# SCFschem.net
KiCad netlist of a schematic drawn in EAGLE
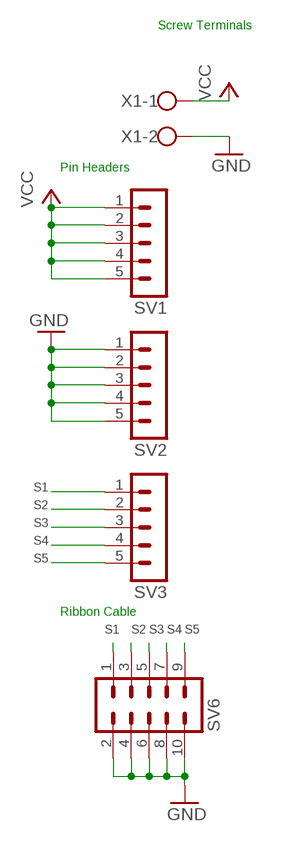
[diagram p0: schematic, sheet 1]

(export (version "E")
  (design (tool "Eeschema 10.0.6"))
  (components
    (comp (ref "SV1")
      (value "MA05-1")
      (footprint "eagle-import:MA05-1")
      (libsource (lib "eagle-import") (part "MA05-1"))
    )
    (comp (ref "SV2")
      (value "MA05-1")
      (footprint "eagle-import:MA05-1")
      (libsource (lib "eagle-import") (part "MA05-1"))
    )
    (comp (ref "SV3")
      (value "MA05-1")
      (footprint "eagle-import:MA05-1")
      (libsource (lib "eagle-import") (part "MA05-1"))
    )
    (comp (ref "SV6")
      (value "MA05-2")
      (footprint "eagle-import:MA05-2")
      (libsource (lib "eagle-import") (part "MA05-2"))
    )
    (comp (ref "X1")
      (value "1X02_5MM_SCREW")
      (footprint "eagle-import:W237-102")
      (fields (field (name "MPN") "237-102"))
      (libsource (lib "eagle-import") (part "1X02_5MM_SCREW"))
    )
  )
  (nets
    (net (code "1") (name "/S1") (class "Default")
      (node (ref "SV3") (pin "1") (pinfunction "1_1") (pintype "passive"))
      (node (ref "SV6") (pin "1") (pinfunction "1_1") (pintype "passive"))
    )
    (net (code "2") (name "/S2") (class "Default")
      (node (ref "SV3") (pin "2") (pinfunction "2_2") (pintype "passive"))
      (node (ref "SV6") (pin "3") (pinfunction "3_3") (pintype "passive"))
    )
    (net (code "3") (name "/S3") (class "Default")
      (node (ref "SV3") (pin "3") (pinfunction "3_3") (pintype "passive"))
      (node (ref "SV6") (pin "5") (pinfunction "5_5") (pintype "passive"))
    )
    (net (code "4") (name "/S4") (class "Default")
      (node (ref "SV3") (pin "4") (pinfunction "4_4") (pintype "passive"))
      (node (ref "SV6") (pin "7") (pinfunction "7_7") (pintype "passive"))
    )
    (net (code "5") (name "/S5") (class "Default")
      (node (ref "SV3") (pin "5") (pinfunction "5_5") (pintype "passive"))
      (node (ref "SV6") (pin "9") (pinfunction "9_9") (pintype "passive"))
    )
    (net (code "6") (name "GND") (class "Default")
      (node (ref "SV2") (pin "1") (pinfunction "1_1") (pintype "passive"))
      (node (ref "SV2") (pin "2") (pinfunction "2_2") (pintype "passive"))
      (node (ref "SV2") (pin "3") (pinfunction "3_3") (pintype "passive"))
      (node (ref "SV2") (pin "4") (pinfunction "4_4") (pintype "passive"))
      (node (ref "SV2") (pin "5") (pinfunction "5_5") (pintype "passive"))
      (node (ref "SV6") (pin "10") (pinfunction "10_10") (pintype "passive"))
      (node (ref "SV6") (pin "2") (pinfunction "2_2") (pintype "passive"))
      (node (ref "SV6") (pin "4") (pinfunction "4_4") (pintype "passive"))
      (node (ref "SV6") (pin "6") (pinfunction "6_6") (pintype "passive"))
      (node (ref "SV6") (pin "8") (pinfunction "8_8") (pintype "passive"))
      (node (ref "X1") (pin "2") (pinfunction "KL_2") (pintype "passive"))
    )
    (net (code "7") (name "VCC") (class "Default")
      (node (ref "SV1") (pin "1") (pinfunction "1_1") (pintype "passive"))
      (node (ref "SV1") (pin "2") (pinfunction "2_2") (pintype "passive"))
      (node (ref "SV1") (pin "3") (pinfunction "3_3") (pintype "passive"))
      (node (ref "SV1") (pin "4") (pinfunction "4_4") (pintype "passive"))
      (node (ref "SV1") (pin "5") (pinfunction "5_5") (pintype "passive"))
      (node (ref "X1") (pin "1") (pinfunction "KL_1") (pintype "passive"))
    )
  )
)
